# Sheet3.net
KiCad netlist of a schematic drawn in Altium Designer
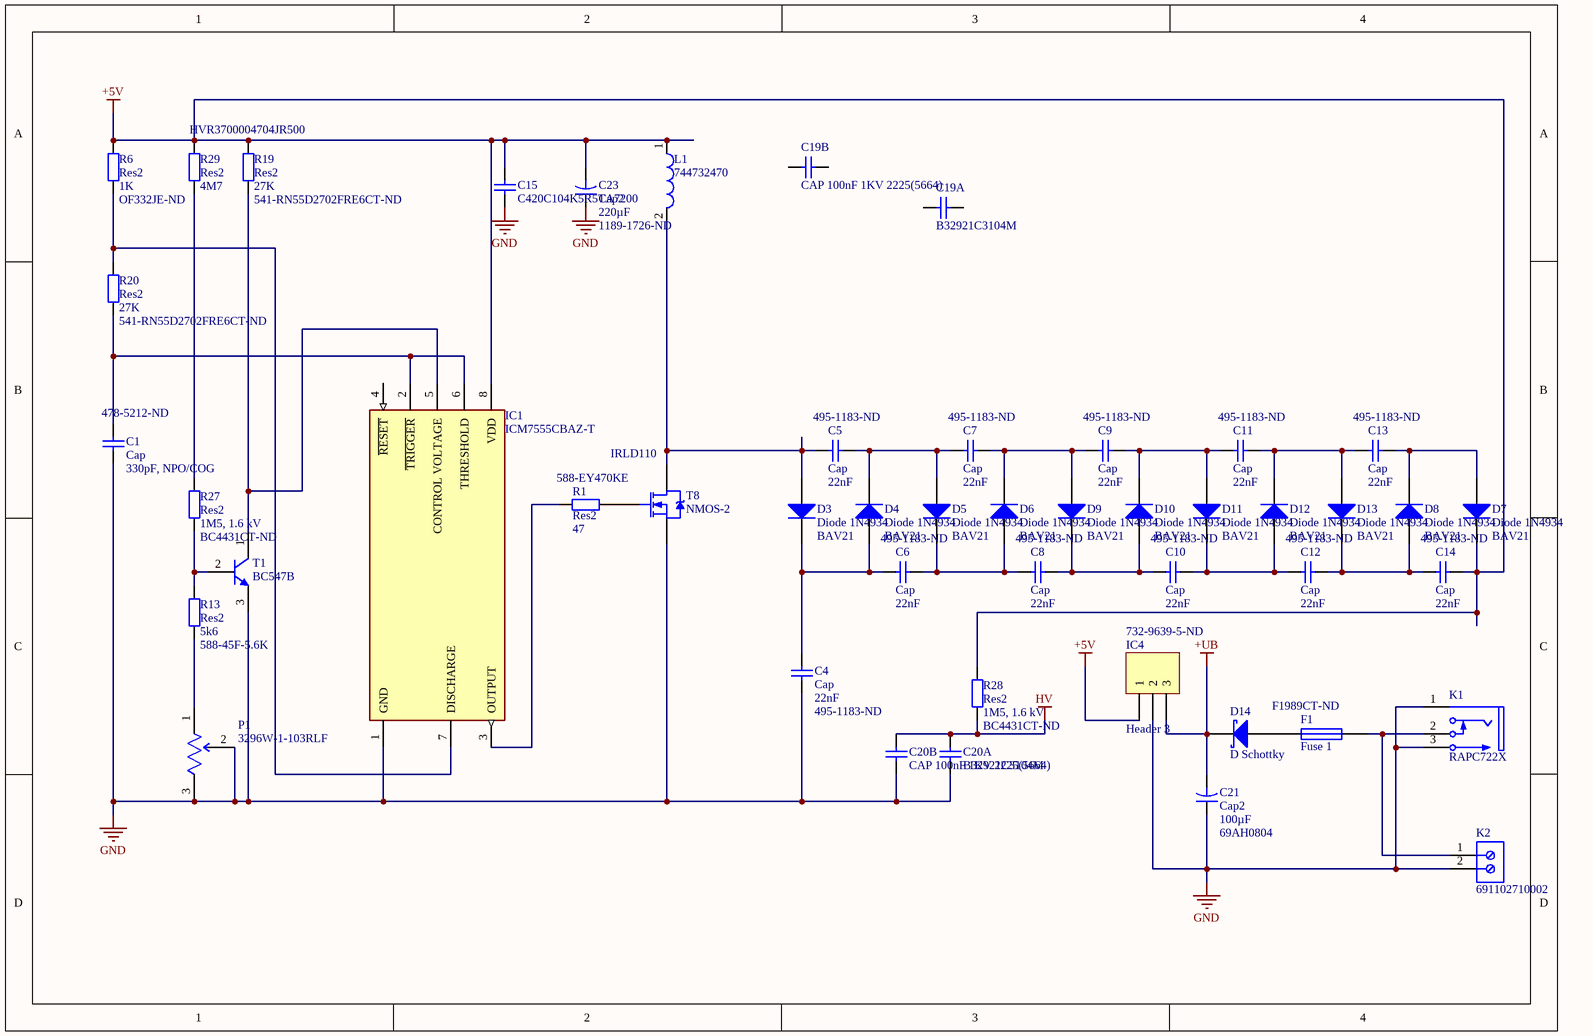
[diagram p0: Sheet3.SchDoc]

(export (version "E")
  (design (tool "Eeschema 10.0.6"))
  (components
    (comp (ref "C1")
      (value "Cap")
      (footprint "RAD-0.3")
      (description "Multilayer Ceramic Capacitor, 330 pF, 100 V,  5%, Radial Leaded, C0G / NP0")
      (fields
        (field (name "ALTIUM_VALUE") "330pF, NPO/COG")
        (field (name "SUPPLIER PART NUMBER 1") "478-5212-ND")
        (field (name "MANUFACTURER") "Kyocera AVX")
        (field (name "MANUFACTURER PART NUMBER") "SR151A331JAR")
        (field (name "PUBLISHER") "Altium Limited")
      )
      (libsource (lib "Miscellaneous Devices") (part "Cap"))
    )
    (comp (ref "C4")
      (value "Cap")
      (footprint "RAD-0.3")
      (description "Cap Film 0.022uF 250V PET 5% (7.2 X 2.5 X 6.5mm) Radial 5mm 125C Bulk")
      (fields
        (field (name "ALTIUM_VALUE") "22nF")
        (field (name "SUPPLIER PART NUMBER 1") "495-1183-ND")
        (field (name "MANUFACTURER") "TDK EPCOS")
        (field (name "MANUFACTURER PART NUMBER") "B32529C3223J000")
        (field (name "PUBLISHER") "Altium Limited")
      )
      (libsource (lib "Miscellaneous Devices") (part "Cap"))
    )
    (comp (ref "C5")
      (value "Cap")
      (footprint "RAD-0.3")
      (description "Cap Film 0.022uF 250V PET 5% (7.2 X 2.5 X 6.5mm) Radial 5mm 125C Bulk")
      (fields
        (field (name "ALTIUM_VALUE") "22nF")
        (field (name "SUPPLIER PART NUMBER 1") "495-1183-ND")
        (field (name "MANUFACTURER") "TDK EPCOS")
        (field (name "MANUFACTURER PART NUMBER") "B32529C3223J000")
        (field (name "PUBLISHER") "Altium Limited")
      )
      (libsource (lib "Miscellaneous Devices") (part "Cap"))
    )
    (comp (ref "C6")
      (value "Cap")
      (footprint "RAD-0.3")
      (description "Cap Film 0.022uF 250V PET 5% (7.2 X 2.5 X 6.5mm) Radial 5mm 125C Bulk")
      (fields
        (field (name "ALTIUM_VALUE") "22nF")
        (field (name "SUPPLIER PART NUMBER 1") "495-1183-ND")
        (field (name "MANUFACTURER") "TDK EPCOS")
        (field (name "MANUFACTURER PART NUMBER") "B32529C3223J000")
        (field (name "PUBLISHER") "Altium Limited")
      )
      (libsource (lib "Miscellaneous Devices") (part "Cap"))
    )
    (comp (ref "C7")
      (value "Cap")
      (footprint "RAD-0.3")
      (description "Cap Film 0.022uF 250V PET 5% (7.2 X 2.5 X 6.5mm) Radial 5mm 125C Bulk")
      (fields
        (field (name "ALTIUM_VALUE") "22nF")
        (field (name "SUPPLIER PART NUMBER 1") "495-1183-ND")
        (field (name "MANUFACTURER") "TDK EPCOS")
        (field (name "MANUFACTURER PART NUMBER") "B32529C3223J000")
        (field (name "PUBLISHER") "Altium Limited")
      )
      (libsource (lib "Miscellaneous Devices") (part "Cap"))
    )
    (comp (ref "C8")
      (value "Cap")
      (footprint "RAD-0.3")
      (description "Cap Film 0.022uF 250V PET 5% (7.2 X 2.5 X 6.5mm) Radial 5mm 125C Bulk")
      (fields
        (field (name "ALTIUM_VALUE") "22nF")
        (field (name "SUPPLIER PART NUMBER 1") "495-1183-ND")
        (field (name "MANUFACTURER") "TDK EPCOS")
        (field (name "MANUFACTURER PART NUMBER") "B32529C3223J000")
        (field (name "PUBLISHER") "Altium Limited")
      )
      (libsource (lib "Miscellaneous Devices") (part "Cap"))
    )
    (comp (ref "C9")
      (value "Cap")
      (footprint "RAD-0.3")
      (description "Cap Film 0.022uF 250V PET 5% (7.2 X 2.5 X 6.5mm) Radial 5mm 125C Bulk")
      (fields
        (field (name "ALTIUM_VALUE") "22nF")
        (field (name "SUPPLIER PART NUMBER 1") "495-1183-ND")
        (field (name "MANUFACTURER") "TDK EPCOS")
        (field (name "MANUFACTURER PART NUMBER") "B32529C3223J000")
        (field (name "PUBLISHER") "Altium Limited")
      )
      (libsource (lib "Miscellaneous Devices") (part "Cap"))
    )
    (comp (ref "C10")
      (value "Cap")
      (footprint "RAD-0.3")
      (description "Cap Film 0.022uF 250V PET 5% (7.2 X 2.5 X 6.5mm) Radial 5mm 125C Bulk")
      (fields
        (field (name "ALTIUM_VALUE") "22nF")
        (field (name "SUPPLIER PART NUMBER 1") "495-1183-ND")
        (field (name "MANUFACTURER") "TDK EPCOS")
        (field (name "MANUFACTURER PART NUMBER") "B32529C3223J000")
        (field (name "PUBLISHER") "Altium Limited")
      )
      (libsource (lib "Miscellaneous Devices") (part "Cap"))
    )
    (comp (ref "C11")
      (value "Cap")
      (footprint "RAD-0.3")
      (description "Cap Film 0.022uF 250V PET 5% (7.2 X 2.5 X 6.5mm) Radial 5mm 125C Bulk")
      (fields
        (field (name "ALTIUM_VALUE") "22nF")
        (field (name "SUPPLIER PART NUMBER 1") "495-1183-ND")
        (field (name "MANUFACTURER") "TDK EPCOS")
        (field (name "MANUFACTURER PART NUMBER") "B32529C3223J000")
        (field (name "PUBLISHER") "Altium Limited")
      )
      (libsource (lib "Miscellaneous Devices") (part "Cap"))
    )
    (comp (ref "C12")
      (value "Cap")
      (footprint "RAD-0.3")
      (description "Cap Film 0.022uF 250V PET 5% (7.2 X 2.5 X 6.5mm) Radial 5mm 125C Bulk")
      (fields
        (field (name "ALTIUM_VALUE") "22nF")
        (field (name "SUPPLIER PART NUMBER 1") "495-1183-ND")
        (field (name "MANUFACTURER") "TDK EPCOS")
        (field (name "MANUFACTURER PART NUMBER") "B32529C3223J000")
        (field (name "PUBLISHER") "Altium Limited")
      )
      (libsource (lib "Miscellaneous Devices") (part "Cap"))
    )
    (comp (ref "C13")
      (value "Cap")
      (footprint "RAD-0.3")
      (description "Cap Film 0.022uF 250V PET 5% (7.2 X 2.5 X 6.5mm) Radial 5mm 125C Bulk")
      (fields
        (field (name "ALTIUM_VALUE") "22nF")
        (field (name "SUPPLIER PART NUMBER 1") "495-1183-ND")
        (field (name "MANUFACTURER") "TDK EPCOS")
        (field (name "MANUFACTURER PART NUMBER") "B32529C3223J000")
        (field (name "PUBLISHER") "Altium Limited")
      )
      (libsource (lib "Miscellaneous Devices") (part "Cap"))
    )
    (comp (ref "C14")
      (value "Cap")
      (footprint "RAD-0.3")
      (description "Cap Film 0.022uF 250V PET 5% (7.2 X 2.5 X 6.5mm) Radial 5mm 125C Bulk")
      (fields
        (field (name "ALTIUM_VALUE") "22nF")
        (field (name "SUPPLIER PART NUMBER 1") "495-1183-ND")
        (field (name "MANUFACTURER") "TDK EPCOS")
        (field (name "MANUFACTURER PART NUMBER") "B32529C3223J000")
        (field (name "PUBLISHER") "Altium Limited")
      )
      (libsource (lib "Miscellaneous Devices") (part "Cap"))
    )
    (comp (ref "C15")
      (value "C420C104K5R5TA7200")
      (footprint "KEMT-C420C104K5R5TA7200-2")
      (description "CAP, Ceramic, 0.1 uF, +/- 10%, 50 V, -55 to 125 degC, 2-Pin THD, RoHS, Tape and Reel")
      (fields (field (name "TOLERANCE") "10%") (field (name "MANUFACTURER") "KEMET"))
      (libsource (lib "Altium Content Vault") (part "CAP-NP-2"))
    )
    (comp (ref "C19A")
      (value "B32921C3104M")
      (footprint "TDK-B32921C3104M")
      (description "EMI Suppression Capacitor (MKP), 0.1 uF, +/- 20%, 305 V, 2-Pin THD, RoHS, Bulk")
      (fields (field (name "MANUFACTURER") "TDK") (field (name "TOLERANCE") "±20%"))
      (libsource (lib "Altium Content Vault") (part "CAP-NP-2"))
    )
    (comp (ref "C19B")
      (value "CAP 100nF 1KV 2225(5664)")
      (footprint "CAPC2225(5664)230_L")
      (description "CAP 100nF 1KV ±10% 2225 (5664 Metric) Thickness 2.2mm SMD")
      (fields (field (name "TOLERANCE") "Â±10%"))
      (libsource (lib "Altium Content Vault") (part "CAP"))
    )
    (comp (ref "C20A")
      (value "B32921C3104M")
      (footprint "TDK-B32921C3104M")
      (description "EMI Suppression Capacitor (MKP), 0.1 uF, +/- 20%, 305 V, 2-Pin THD, RoHS, Bulk")
      (fields (field (name "MANUFACTURER") "TDK") (field (name "TOLERANCE") "±20%"))
      (libsource (lib "Altium Content Vault") (part "CAP-NP-2"))
    )
    (comp (ref "C20B")
      (value "CAP 100nF 1KV 2225(5664)")
      (footprint "CAPC2225(5664)230_L")
      (description "CAP 100nF 1KV ±10% 2225 (5664 Metric) Thickness 2.2mm SMD")
      (fields (field (name "TOLERANCE") "Â±10%"))
      (libsource (lib "Altium Content Vault") (part "CAP"))
    )
    (comp (ref "C21")
      (value "Cap2")
      (footprint "CAPR5-4X5")
      (description "Cap Aluminum 100uF 25V 20% (6.3 X 11mm) Radial 5mm 190mA 2500 hr 85C Ammo Pack")
      (fields
        (field (name "ALTIUM_VALUE") "100µF")
        (field (name "SUPPLIER PART NUMBER 1") "69AH0804")
        (field (name "MANUFACTURER") "Vishay BCcomponents")
        (field (name "MANUFACTURER PART NUMBER") "MAL203836101E3")
        (field (name "PUBLISHER") "Altium Limited")
      )
      (libsource (lib "Miscellaneous Devices") (part "Cap2"))
    )
    (comp (ref "C23")
      (value "Cap2")
      (footprint "CAPR5-4X5")
      (description "Rubycon Aluminium Electrolytic Capacitor 220F 16 V dc 6.3mm Through Hole series ZLH lifetime 6000h")
      (fields
        (field (name "ALTIUM_VALUE") "220µF")
        (field (name "SUPPLIER PART NUMBER 1") "1189-1726-ND")
        (field (name "MANUFACTURER") "Rubycon")
        (field (name "MANUFACTURER PART NUMBER") "16ZLH220MEFC6.3X11")
        (field (name "PUBLISHER") "Altium Limited")
      )
      (libsource (lib "Miscellaneous Devices") (part "Cap2"))
    )
    (comp (ref "D3")
      (value "Diode 1N4934")
      (footprint "DO-41")
      (description "DIODE, SMALL SIGNAL, DO-35")
      (fields
        (field (name "SUPPLIER PART NUMBER 1") "BAV21")
        (field (name "MANUFACTURER") "NXP Semiconductors")
        (field (name "MANUFACTURER PART NUMBER") "BAV21")
        (field (name "PUBLISHER") "Altium Limited")
      )
      (libsource (lib "Miscellaneous Devices") (part "Diode 1N4934"))
    )
    (comp (ref "D4")
      (value "Diode 1N4934")
      (footprint "DO-41")
      (description "DIODE, SMALL SIGNAL, DO-35")
      (fields
        (field (name "SUPPLIER PART NUMBER 1") "BAV21")
        (field (name "MANUFACTURER") "NXP Semiconductors")
        (field (name "MANUFACTURER PART NUMBER") "BAV21")
        (field (name "PUBLISHER") "Altium Limited")
      )
      (libsource (lib "Miscellaneous Devices") (part "Diode 1N4934"))
    )
    (comp (ref "D5")
      (value "Diode 1N4934")
      (footprint "DO-41")
      (description "DIODE, SMALL SIGNAL, DO-35")
      (fields
        (field (name "SUPPLIER PART NUMBER 1") "BAV21")
        (field (name "MANUFACTURER") "NXP Semiconductors")
        (field (name "MANUFACTURER PART NUMBER") "BAV21")
        (field (name "PUBLISHER") "Altium Limited")
      )
      (libsource (lib "Miscellaneous Devices") (part "Diode 1N4934"))
    )
    (comp (ref "D6")
      (value "Diode 1N4934")
      (footprint "DO-41")
      (description "DIODE, SMALL SIGNAL, DO-35")
      (fields
        (field (name "SUPPLIER PART NUMBER 1") "BAV21")
        (field (name "MANUFACTURER") "NXP Semiconductors")
        (field (name "MANUFACTURER PART NUMBER") "BAV21")
        (field (name "PUBLISHER") "Altium Limited")
      )
      (libsource (lib "Miscellaneous Devices") (part "Diode 1N4934"))
    )
    (comp (ref "D7")
      (value "Diode 1N4934")
      (footprint "DO-41")
      (description "DIODE, SMALL SIGNAL, DO-35")
      (fields
        (field (name "SUPPLIER PART NUMBER 1") "BAV21")
        (field (name "MANUFACTURER") "NXP Semiconductors")
        (field (name "MANUFACTURER PART NUMBER") "BAV21")
        (field (name "PUBLISHER") "Altium Limited")
      )
      (libsource (lib "Miscellaneous Devices") (part "Diode 1N4934"))
    )
    (comp (ref "D8")
      (value "Diode 1N4934")
      (footprint "DO-41")
      (description "DIODE, SMALL SIGNAL, DO-35")
      (fields
        (field (name "SUPPLIER PART NUMBER 1") "BAV21")
        (field (name "MANUFACTURER") "NXP Semiconductors")
        (field (name "MANUFACTURER PART NUMBER") "BAV21")
        (field (name "PUBLISHER") "Altium Limited")
      )
      (libsource (lib "Miscellaneous Devices") (part "Diode 1N4934"))
    )
    (comp (ref "D9")
      (value "Diode 1N4934")
      (footprint "DO-41")
      (description "DIODE, SMALL SIGNAL, DO-35")
      (fields
        (field (name "SUPPLIER PART NUMBER 1") "BAV21")
        (field (name "MANUFACTURER") "NXP Semiconductors")
        (field (name "MANUFACTURER PART NUMBER") "BAV21")
        (field (name "PUBLISHER") "Altium Limited")
      )
      (libsource (lib "Miscellaneous Devices") (part "Diode 1N4934"))
    )
    (comp (ref "D10")
      (value "Diode 1N4934")
      (footprint "DO-41")
      (description "DIODE, SMALL SIGNAL, DO-35")
      (fields
        (field (name "SUPPLIER PART NUMBER 1") "BAV21")
        (field (name "MANUFACTURER") "NXP Semiconductors")
        (field (name "MANUFACTURER PART NUMBER") "BAV21")
        (field (name "PUBLISHER") "Altium Limited")
      )
      (libsource (lib "Miscellaneous Devices") (part "Diode 1N4934"))
    )
    (comp (ref "D11")
      (value "Diode 1N4934")
      (footprint "DO-41")
      (description "DIODE, SMALL SIGNAL, DO-35")
      (fields
        (field (name "SUPPLIER PART NUMBER 1") "BAV21")
        (field (name "MANUFACTURER") "NXP Semiconductors")
        (field (name "MANUFACTURER PART NUMBER") "BAV21")
        (field (name "PUBLISHER") "Altium Limited")
      )
      (libsource (lib "Miscellaneous Devices") (part "Diode 1N4934"))
    )
    (comp (ref "D12")
      (value "Diode 1N4934")
      (footprint "DO-41")
      (description "DIODE, SMALL SIGNAL, DO-35")
      (fields
        (field (name "SUPPLIER PART NUMBER 1") "BAV21")
        (field (name "MANUFACTURER") "NXP Semiconductors")
        (field (name "MANUFACTURER PART NUMBER") "BAV21")
        (field (name "PUBLISHER") "Altium Limited")
      )
      (libsource (lib "Miscellaneous Devices") (part "Diode 1N4934"))
    )
    (comp (ref "D13")
      (value "Diode 1N4934")
      (footprint "DO-41")
      (description "DIODE, SMALL SIGNAL, DO-35")
      (fields
        (field (name "SUPPLIER PART NUMBER 1") "BAV21")
        (field (name "MANUFACTURER") "NXP Semiconductors")
        (field (name "MANUFACTURER PART NUMBER") "BAV21")
        (field (name "PUBLISHER") "Altium Limited")
      )
      (libsource (lib "Miscellaneous Devices") (part "Diode 1N4934"))
    )
    (comp (ref "D14")
      (value "D Schottky")
      (footprint "SMB")
      (description "Schottky Diode")
      (fields (field (name "PUBLISHER") "Altium Limited"))
      (libsource (lib "Miscellaneous Devices") (part "D Schottky"))
    )
    (comp (ref "F1")
      (value "Fuse 1")
      (footprint "PIN-W2/E2.8")
      (description "PTC Resettable Fuse 0.5A(hold) 1A(trip) 60VDC 40A 0.77W 4s 0.5Ohm Radial 7.9 X 3.1mm Ammo Pack")
      (fields
        (field (name "SUPPLIER PART NUMBER 1") "F1989CT-ND")
        (field (name "MANUFACTURER") "Littelfuse")
        (field (name "MANUFACTURER PART NUMBER") "60R050XPR")
        (field (name "PUBLISHER") "Altium Limited")
      )
      (libsource (lib "Miscellaneous Devices") (part "Fuse 1"))
    )
    (comp (ref "IC1")
      (value "ICM7555CBAZ-T")
      (footprint "FP-M8_15-MFG")
      (description "IC OSC SINGLE TIMER 1MHZ 8-SOIC")
      (libsource (lib "Altium Content Vault") (part "fe4693fe04683744476327e546b5574"))
    )
    (comp (ref "IC4")
      (value "Header 3")
      (footprint "HDR1X3")
      (fields
        (field (name "SUPPLIER PART NUMBER 1") "732-9639-5-ND")
        (field (name "MANUFACTURER") "Wurth Electronics")
        (field (name "MANUFACTURER PART NUMBER") "173010578")
        (field (name "PUBLISHER") "Altium Limited")
      )
      (libsource (lib "Miscellaneous Connectors") (part "Header 3"))
    )
    (comp (ref "K1")
      (value "RAPC722X")
      (footprint "SWITCH-RAPC712X-3_V")
      (description "Power Jack, 5 A, 3-Pin THD, RoHS, Bulk")
      (fields (field (name "MANUFACTURER") "Switchcraft"))
      (libsource (lib "Altium Content Vault") (part "SWITCH-RAPC712X-3"))
    )
    (comp (ref "K2")
      (value "691102710002")
      (footprint "691102710002")
      (description "Series 102 - 5.00 mm Horizontal Entry Modular with Pressure Clamp WR-TBL, 2 pin")
      (fields (field (name "MANUFACTURER") "Wurth Elektronik") (field (name "PUBLISHER") "WurthElektronik"))
      (libsource (lib "Altium Content Vault") (part "WE-CN-1P-F-TB2"))
    )
    (comp (ref "L1")
      (value "744732470")
      (footprint "WE-TI-LM-STBG")
      (description "Radial Leaded Wire Wound Inductor WE-TI, L = 47.0 µH")
      (libsource (lib "Altium Content Vault") (part "PAS-IND-INDUCTOR-2"))
    )
    (comp (ref "P1")
      (value "3296W-1-103RLF")
      (footprint "FP-3296W-MFG")
      (description "TRIMMER 10K OHM 0.5W PC PIN TOP")
      (fields (field (name "TOLERANCE") "10%"))
      (libsource (lib "Altium Content Vault") (part "194907ebf2981c0cdd5d9631a0af656"))
    )
    (comp (ref "R1")
      (value "Res2")
      (footprint "AXIAL-0.4")
      (fields
        (field (name "ALTIUM_VALUE") "47")
        (field (name "SUPPLIER PART NUMBER 1") "588-EY470KE")
        (field (name "MANUFACTURER") "Ohmite")
        (field (name "MANUFACTURER PART NUMBER") "EY470KE")
        (field (name "TOLERANCE") "10%")
        (field (name "PUBLISHER") "Altium Limited")
      )
      (libsource (lib "") (part "Res2_2"))
    )
    (comp (ref "R6")
      (value "Res2")
      (footprint "AXIAL-0.4")
      (description "Resistor;  Carbon Composition;  Res 3.3 Kilohms;  Pwr-Rtg 0.5 W;  Tol 5%;  Axial")
      (fields
        (field (name "ALTIUM_VALUE") "1K")
        (field (name "SUPPLIER PART NUMBER 1") "OF332JE-ND")
        (field (name "MANUFACTURER") "Ohmite")
        (field (name "MANUFACTURER PART NUMBER") "OF332JE")
        (field (name "PUBLISHER") "Altium Limited")
      )
      (libsource (lib "") (part "Res2_1"))
    )
    (comp (ref "R13")
      (value "Res2")
      (footprint "AXIAL-0.4")
      (description "RES 5.6K OHM 5W 1% AXIAL")
      (fields
        (field (name "ALTIUM_VALUE") "5k6")
        (field (name "SUPPLIER PART NUMBER 1") "588-45F-5.6K")
        (field (name "MANUFACTURER") "Ohmite")
        (field (name "MANUFACTURER PART NUMBER") "45F5K6")
        (field (name "PUBLISHER") "Altium Limited")
      )
      (libsource (lib "Miscellaneous Devices") (part "Res2"))
    )
    (comp (ref "R19")
      (value "Res2")
      (footprint "AXIAL-0.4")
      (description "RES 27K OHM 1/8W 1% AXIAL")
      (fields
        (field (name "ALTIUM_VALUE") "27K")
        (field (name "SUPPLIER PART NUMBER 1") "541-RN55D2702FRE6CT-ND")
        (field (name "MANUFACTURER") "Vishay Dale")
        (field (name "MANUFACTURER PART NUMBER") "RN55D2702FRE6")
        (field (name "PUBLISHER") "Altium Limited")
      )
      (libsource (lib "Miscellaneous Devices") (part "Res2"))
    )
    (comp (ref "R20")
      (value "Res2")
      (footprint "AXIAL-0.4")
      (description "RES 27K OHM 1/8W 1% AXIAL")
      (fields
        (field (name "ALTIUM_VALUE") "27K")
        (field (name "SUPPLIER PART NUMBER 1") "541-RN55D2702FRE6CT-ND")
        (field (name "MANUFACTURER") "Vishay Dale")
        (field (name "MANUFACTURER PART NUMBER") "RN55D2702FRE6")
        (field (name "PUBLISHER") "Altium Limited")
      )
      (libsource (lib "Miscellaneous Devices") (part "Res2"))
    )
    (comp (ref "R27")
      (value "Res2")
      (footprint "AXIAL-0.4")
      (description "VISHAY - HVR2500001504JA100 - MOTSTÅND, 1M5")
      (fields
        (field (name "ALTIUM_VALUE") "1M5, 1.6 kV")
        (field (name "SUPPLIER PART NUMBER 1") "BC4431CT-ND")
        (field (name "MANUFACTURER") "Vishay BCcomponents")
        (field (name "MANUFACTURER PART NUMBER") "HVR2500001504JA100")
        (field (name "PUBLISHER") "Altium Limited")
      )
      (libsource (lib "Miscellaneous Devices") (part "Res2"))
    )
    (comp (ref "R28")
      (value "Res2")
      (footprint "AXIAL-0.4")
      (description "VISHAY - HVR2500001504JA100 - MOTSTÅND, 1M5")
      (fields
        (field (name "ALTIUM_VALUE") "1M5, 1.6 kV")
        (field (name "SUPPLIER PART NUMBER 1") "BC4431CT-ND")
        (field (name "MANUFACTURER") "Vishay BCcomponents")
        (field (name "MANUFACTURER PART NUMBER") "HVR2500001504JA100")
        (field (name "PUBLISHER") "Altium Limited")
      )
      (libsource (lib "Miscellaneous Devices") (part "Res2"))
    )
    (comp (ref "R29")
      (value "Res2")
      (footprint "AXIAL-0.4")
      (description "RES 4.7M OHM 1/2W 5% AXIAL")
      (fields
        (field (name "ALTIUM_VALUE") "4M7")
        (field (name "SUPPLIER PART NUMBER 1") "HVR3700004704JR500")
        (field (name "MANUFACTURER") "Vishay BCcomponents")
        (field (name "MANUFACTURER PART NUMBER") "HVR3700004704JR500")
        (field (name "PUBLISHER") "Altium Limited")
      )
      (libsource (lib "Miscellaneous Devices") (part "Res2"))
    )
    (comp (ref "T1")
      (value "BC547B")
      (footprint "ONSC-TO-92-3-29-11")
      (description "Amplifier Transistor, NPN Silicon, 3-Pin TO-92, Bulk Box")
      (fields (field (name "MANUFACTURER") "On Semiconductor"))
      (libsource (lib "Altium Content Vault") (part "ONSC-NPN-C1B2E3-3"))
    )
    (comp (ref "T8")
      (value "NMOS-2")
      (footprint "TO-220AB")
      (description "MOSFET N-CH 100V 1A 4-DIP")
      (fields
        (field (name "SUPPLIER PART NUMBER 1") "IRLD110")
        (field (name "MANUFACTURER") "Vishay Siliconix")
        (field (name "MANUFACTURER PART NUMBER") "IRLD110")
        (field (name "PUBLISHER") "Altium Limited")
      )
      (libsource (lib "Miscellaneous Devices") (part "NMOS-2"))
    )
  )
  (nets
    (net (code "1") (name "+5V") (class "Default")
      (node (ref "C14") (pin "2") (pinfunction "2_2") (pintype "passive"))
      (node (ref "C15") (pin "2") (pinfunction "2_2") (pintype "passive"))
      (node (ref "C23") (pin "2") (pinfunction "2_2") (pintype "passive"))
      (node (ref "D7") (pin "2") (pinfunction "K_2") (pintype "passive"))
      (node (ref "IC1") (pin "8") (pinfunction "VDD_8") (pintype "power_in"))
      (node (ref "IC4") (pin "1") (pinfunction "1_1") (pintype "passive"))
      (node (ref "L1") (pin "1") (pinfunction "1_1") (pintype "passive"))
      (node (ref "R19") (pin "2") (pinfunction "2_2") (pintype "passive"))
      (node (ref "R28") (pin "2") (pinfunction "2_2") (pintype "passive"))
      (node (ref "R29") (pin "2") (pinfunction "2_2") (pintype "passive"))
      (node (ref "R6") (pin "1") (pinfunction "1_1") (pintype "passive"))
    )
    (net (code "2") (name "+UB") (class "Default")
      (node (ref "C21") (pin "2") (pinfunction "2_2") (pintype "passive"))
      (node (ref "D14") (pin "2") (pinfunction "K_2") (pintype "passive"))
      (node (ref "IC4") (pin "3") (pinfunction "3_3") (pintype "passive"))
    )
    (net (code "3") (name "GND") (class "Default")
      (node (ref "C1") (pin "1") (pinfunction "1_1") (pintype "passive"))
      (node (ref "C15") (pin "1") (pinfunction "1_1") (pintype "passive"))
      (node (ref "C20A") (pin "1") (pinfunction "1_1") (pintype "passive"))
      (node (ref "C20B") (pin "1") (pinfunction "1_1") (pintype "passive"))
      (node (ref "C21") (pin "1") (pinfunction "1_1") (pintype "passive"))
      (node (ref "C23") (pin "1") (pinfunction "1_1") (pintype "passive"))
      (node (ref "C4") (pin "1") (pinfunction "1_1") (pintype "passive"))
      (node (ref "IC1") (pin "1") (pinfunction "GND_1") (pintype "power_in"))
      (node (ref "IC4") (pin "2") (pinfunction "2_2") (pintype "passive"))
      (node (ref "K1") (pin "1") (pinfunction "1_1") (pintype "passive"))
      (node (ref "K1") (pin "3") (pinfunction "3_3") (pintype "passive"))
      (node (ref "K2") (pin "2") (pinfunction "2_2") (pintype "passive"))
      (node (ref "P1") (pin "2") (pinfunction "WIPER_2") (pintype "passive"))
      (node (ref "P1") (pin "3") (pinfunction "CW_3") (pintype "passive"))
      (node (ref "T1") (pin "3") (pinfunction "E_3") (pintype "passive"))
      (node (ref "T8") (pin "3") (pinfunction "S_3") (pintype "passive"))
    )
    (net (code "4") (name "HV") (class "Default")
      (node (ref "C20A") (pin "2") (pinfunction "2_2") (pintype "passive"))
      (node (ref "C20B") (pin "2") (pinfunction "2_2") (pintype "passive"))
      (node (ref "R28") (pin "1") (pinfunction "1_1") (pintype "passive"))
    )
    (net (code "5") (name "Net-(D3-A)") (class "Default")
      (node (ref "C5") (pin "1") (pinfunction "1_1") (pintype "passive"))
      (node (ref "D3") (pin "1") (pinfunction "A_1") (pintype "passive"))
      (node (ref "L1") (pin "2") (pinfunction "2_2") (pintype "passive"))
      (node (ref "T8") (pin "2") (pinfunction "D_2") (pintype "passive"))
    )
    (net (code "6") (name "Net-(D3-K)") (class "Default")
      (node (ref "C4") (pin "2") (pinfunction "2_2") (pintype "passive"))
      (node (ref "C6") (pin "1") (pinfunction "1_1") (pintype "passive"))
      (node (ref "D3") (pin "2") (pinfunction "K_2") (pintype "passive"))
      (node (ref "D4") (pin "1") (pinfunction "A_1") (pintype "passive"))
    )
    (net (code "7") (name "Net-(D4-K)") (class "Default")
      (node (ref "C5") (pin "2") (pinfunction "2_2") (pintype "passive"))
      (node (ref "C7") (pin "1") (pinfunction "1_1") (pintype "passive"))
      (node (ref "D4") (pin "2") (pinfunction "K_2") (pintype "passive"))
      (node (ref "D5") (pin "1") (pinfunction "A_1") (pintype "passive"))
    )
    (net (code "8") (name "Net-(D5-K)") (class "Default")
      (node (ref "C6") (pin "2") (pinfunction "2_2") (pintype "passive"))
      (node (ref "C8") (pin "1") (pinfunction "1_1") (pintype "passive"))
      (node (ref "D5") (pin "2") (pinfunction "K_2") (pintype "passive"))
      (node (ref "D6") (pin "1") (pinfunction "A_1") (pintype "passive"))
    )
    (net (code "9") (name "Net-(D6-K)") (class "Default")
      (node (ref "C7") (pin "2") (pinfunction "2_2") (pintype "passive"))
      (node (ref "C9") (pin "1") (pinfunction "1_1") (pintype "passive"))
      (node (ref "D6") (pin "2") (pinfunction "K_2") (pintype "passive"))
      (node (ref "D9") (pin "1") (pinfunction "A_1") (pintype "passive"))
    )
    (net (code "10") (name "Net-(D7-A)") (class "Default")
      (node (ref "C13") (pin "2") (pinfunction "2_2") (pintype "passive"))
      (node (ref "D7") (pin "1") (pinfunction "A_1") (pintype "passive"))
      (node (ref "D8") (pin "2") (pinfunction "K_2") (pintype "passive"))
    )
    (net (code "11") (name "Net-(D10-A)") (class "Default")
      (node (ref "C10") (pin "1") (pinfunction "1_1") (pintype "passive"))
      (node (ref "C8") (pin "2") (pinfunction "2_2") (pintype "passive"))
      (node (ref "D10") (pin "1") (pinfunction "A_1") (pintype "passive"))
      (node (ref "D9") (pin "2") (pinfunction "K_2") (pintype "passive"))
    )
    (net (code "12") (name "Net-(D10-K)") (class "Default")
      (node (ref "C11") (pin "1") (pinfunction "1_1") (pintype "passive"))
      (node (ref "C9") (pin "2") (pinfunction "2_2") (pintype "passive"))
      (node (ref "D10") (pin "2") (pinfunction "K_2") (pintype "passive"))
      (node (ref "D11") (pin "1") (pinfunction "A_1") (pintype "passive"))
    )
    (net (code "13") (name "Net-(D11-K)") (class "Default")
      (node (ref "C10") (pin "2") (pinfunction "2_2") (pintype "passive"))
      (node (ref "C12") (pin "1") (pinfunction "1_1") (pintype "passive"))
      (node (ref "D11") (pin "2") (pinfunction "K_2") (pintype "passive"))
      (node (ref "D12") (pin "1") (pinfunction "A_1") (pintype "passive"))
    )
    (net (code "14") (name "Net-(D12-K)") (class "Default")
      (node (ref "C11") (pin "2") (pinfunction "2_2") (pintype "passive"))
      (node (ref "C13") (pin "1") (pinfunction "1_1") (pintype "passive"))
      (node (ref "D12") (pin "2") (pinfunction "K_2") (pintype "passive"))
      (node (ref "D13") (pin "1") (pinfunction "A_1") (pintype "passive"))
    )
    (net (code "15") (name "Net-(D13-K)") (class "Default")
      (node (ref "C12") (pin "2") (pinfunction "2_2") (pintype "passive"))
      (node (ref "C14") (pin "1") (pinfunction "1_1") (pintype "passive"))
      (node (ref "D13") (pin "2") (pinfunction "K_2") (pintype "passive"))
      (node (ref "D8") (pin "1") (pinfunction "A_1") (pintype "passive"))
    )
    (net (code "16") (name "Net-(D14-A)") (class "Default")
      (node (ref "D14") (pin "1") (pinfunction "A_1") (pintype "passive"))
      (node (ref "F1") (pin "1") (pinfunction "1_1") (pintype "passive"))
    )
    (net (code "17") (name "Net-(F1-Pad2)") (class "Default")
      (node (ref "F1") (pin "2") (pinfunction "2_2") (pintype "passive"))
      (node (ref "K1") (pin "2") (pinfunction "2_2") (pintype "passive"))
      (node (ref "K2") (pin "1") (pinfunction "1_1") (pintype "passive"))
    )
    (net (code "18") (name "Net-(IC1-CONTROL_VOLTAGE)") (class "Default")
      (node (ref "IC1") (pin "5") (pinfunction "CONTROL_VOLTAGE_5") (pintype "tri_state"))
      (node (ref "R19") (pin "1") (pinfunction "1_1") (pintype "passive"))
      (node (ref "T1") (pin "1") (pinfunction "C_1") (pintype "passive"))
    )
    (net (code "19") (name "Net-(IC1-DISCHARGE)") (class "Default")
      (node (ref "IC1") (pin "7") (pinfunction "DISCHARGE_7") (pintype "open_collector"))
      (node (ref "R20") (pin "2") (pinfunction "2_2") (pintype "passive"))
      (node (ref "R6") (pin "2") (pinfunction "2_2") (pintype "passive"))
    )
    (net (code "20") (name "Net-(IC1-OUTPUT)") (class "Default")
      (node (ref "IC1") (pin "3") (pinfunction "OUTPUT_3") (pintype "output"))
      (node (ref "R1") (pin "1") (pinfunction "1_1") (pintype "passive"))
    )
    (net (code "21") (name "Net-(IC1-THRESHOLD)") (class "Default")
      (node (ref "C1") (pin "2") (pinfunction "2_2") (pintype "passive"))
      (node (ref "IC1") (pin "2") (pinfunction "~{TRIGGER}_2") (pintype "tri_state"))
      (node (ref "IC1") (pin "6") (pinfunction "THRESHOLD_6") (pintype "tri_state"))
      (node (ref "R20") (pin "1") (pinfunction "1_1") (pintype "passive"))
    )
    (net (code "22") (name "Net-(P1-CCW)") (class "Default")
      (node (ref "P1") (pin "1") (pinfunction "CCW_1") (pintype "passive"))
      (node (ref "R13") (pin "1") (pinfunction "1_1") (pintype "passive"))
    )
    (net (code "23") (name "Net-(R27-Pad2)") (class "Default")
      (node (ref "R27") (pin "2") (pinfunction "2_2") (pintype "passive"))
      (node (ref "R29") (pin "1") (pinfunction "1_1") (pintype "passive"))
    )
    (net (code "24") (name "Net-(T1-B)") (class "Default")
      (node (ref "R13") (pin "2") (pinfunction "2_2") (pintype "passive"))
      (node (ref "R27") (pin "1") (pinfunction "1_1") (pintype "passive"))
      (node (ref "T1") (pin "2") (pinfunction "B_2") (pintype "passive"))
    )
    (net (code "25") (name "Net-(T8-G)") (class "Default")
      (node (ref "R1") (pin "2") (pinfunction "2_2") (pintype "passive"))
      (node (ref "T8") (pin "1") (pinfunction "G_1") (pintype "passive"))
    )
    (net (code "26") (name "unconnected-(C19A-Pad1)") (class "Default")
      (node (ref "C19A") (pin "1") (pinfunction "1_1") (pintype "passive"))
    )
    (net (code "27") (name "unconnected-(C19A-Pad2)") (class "Default")
      (node (ref "C19A") (pin "2") (pinfunction "2_2") (pintype "passive"))
    )
    (net (code "28") (name "unconnected-(C19B-Pad1)") (class "Default")
      (node (ref "C19B") (pin "1") (pinfunction "1_1") (pintype "passive"))
    )
    (net (code "29") (name "unconnected-(C19B-Pad2)") (class "Default")
      (node (ref "C19B") (pin "2") (pinfunction "2_2") (pintype "passive"))
    )
    (net (code "30") (name "unconnected-(IC1-~{RESET}-Pad4)") (class "Default")
      (node (ref "IC1") (pin "4") (pinfunction "~{RESET}_4") (pintype "input"))
    )
  )
)
